# ltc2934_platine.net
KiCad netlist of a schematic drawn in EAGLE
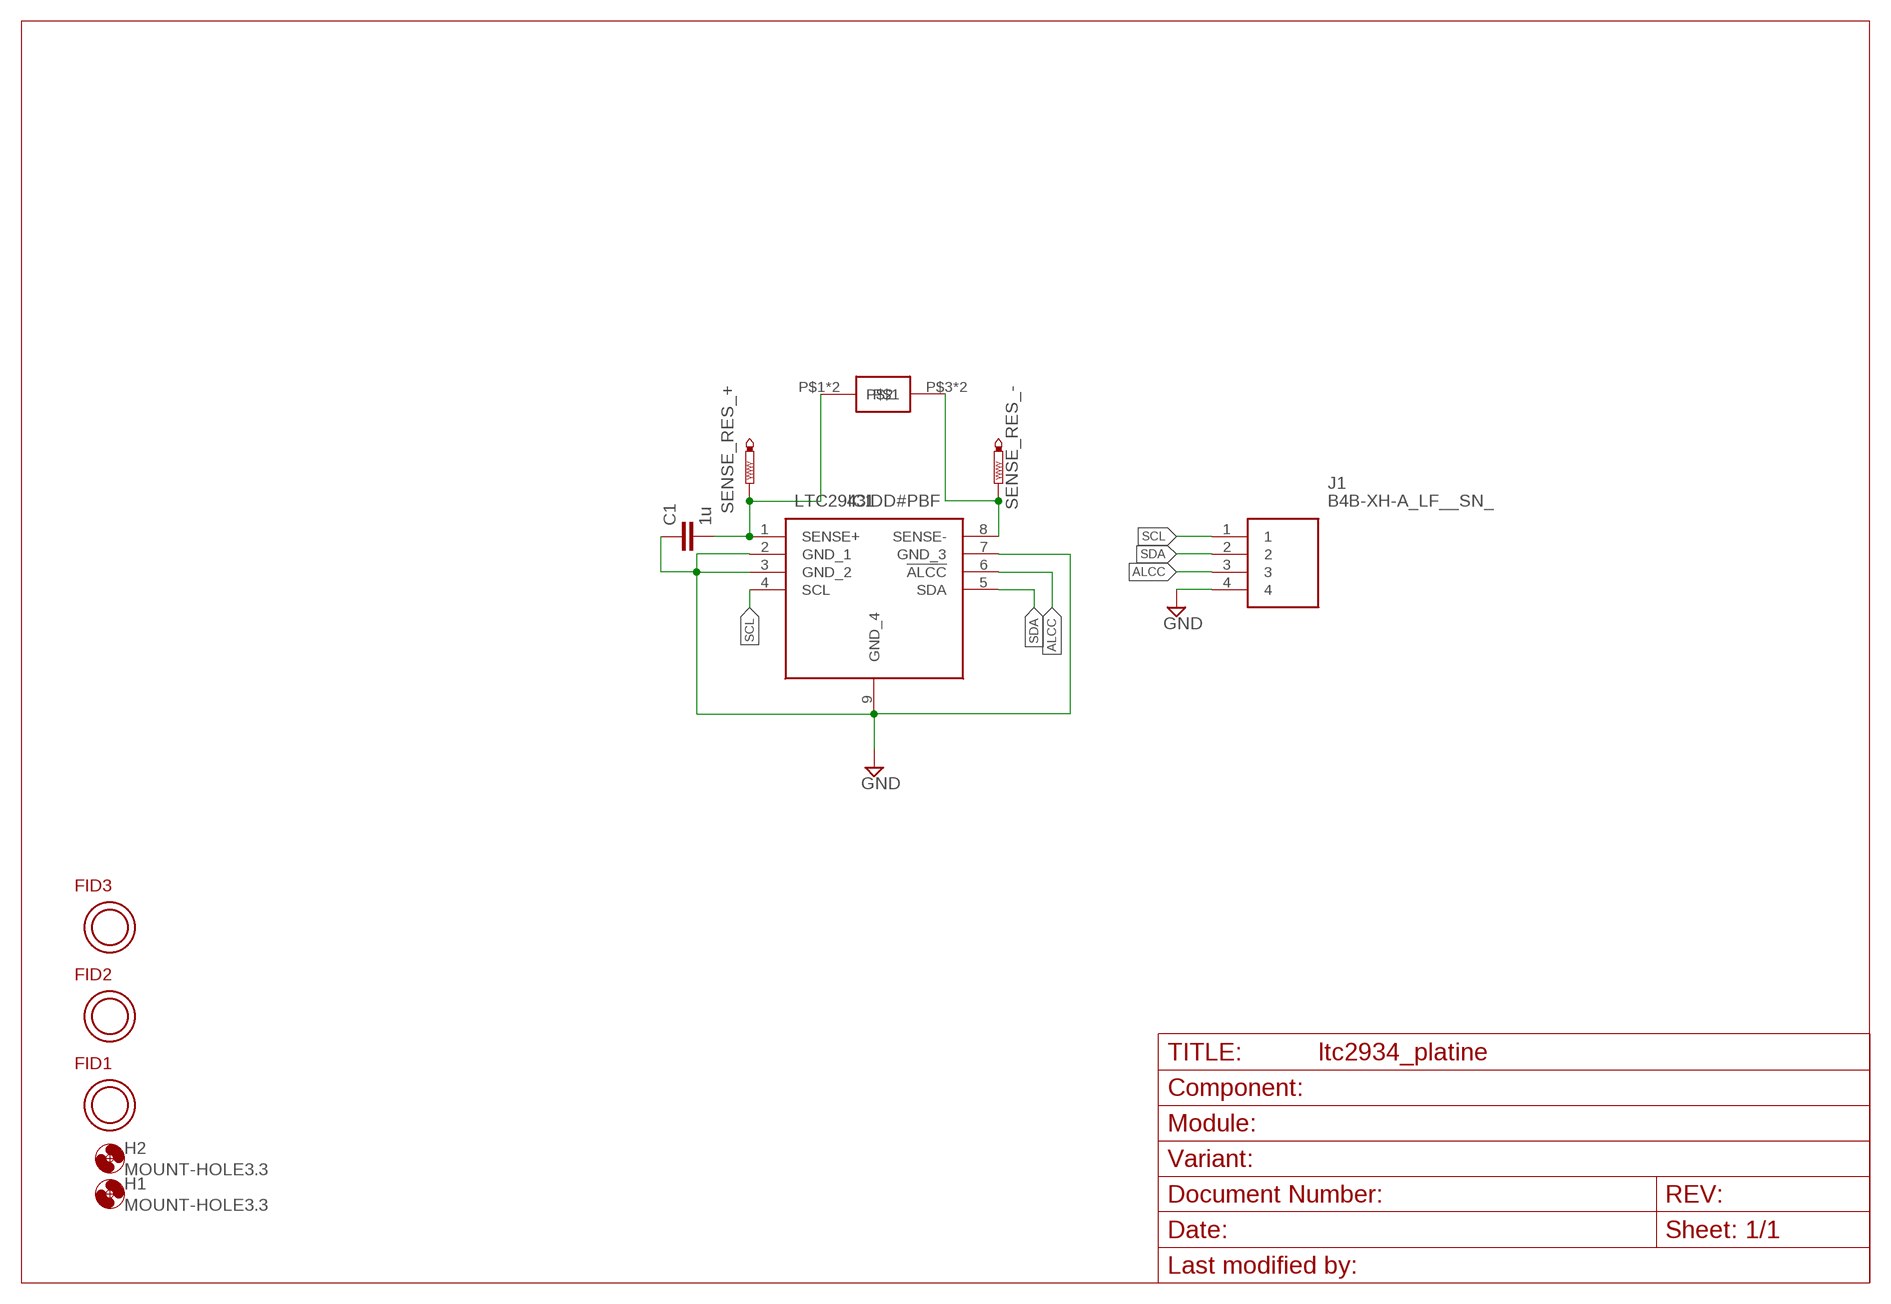
[diagram p0: schematic, sheet 1]

(export (version "E")
  (design (tool "Eeschema 10.0.6"))
  (components
    (comp (ref "C1")
      (value "1u")
      (footprint "eagle-import:C1206")
      (libsource (lib "eagle-import") (part "C-EUC1206"))
    )
    (comp (ref "FID1")
      (value "OPEN-PNP-FIDUCIAL")
      (footprint "eagle-import:OPEN-PNP-FIDUCIAL")
      (libsource (lib "eagle-import") (part "OPEN-PNP-FIDUCIAL"))
    )
    (comp (ref "FID2")
      (value "OPEN-PNP-FIDUCIAL")
      (footprint "eagle-import:OPEN-PNP-FIDUCIAL")
      (libsource (lib "eagle-import") (part "OPEN-PNP-FIDUCIAL"))
    )
    (comp (ref "FID3")
      (value "OPEN-PNP-FIDUCIAL")
      (footprint "eagle-import:OPEN-PNP-FIDUCIAL")
      (libsource (lib "eagle-import") (part "OPEN-PNP-FIDUCIAL"))
    )
    (comp (ref "H1")
      (value "MOUNT-HOLE3.3")
      (footprint "eagle-import:3,3")
      (libsource (lib "eagle-import") (part "MOUNT-HOLE3.3"))
    )
    (comp (ref "H2")
      (value "MOUNT-HOLE3.3")
      (footprint "eagle-import:3,3")
      (libsource (lib "eagle-import") (part "MOUNT-HOLE3.3"))
    )
    (comp (ref "IC1")
      (value "LTC2943IDD#PBF")
      (footprint "eagle-import:SON50P300X300X80-9N")
      (fields (field (name "MOUSER_PART_NUMBER") "584-LTC2943IDD#PBF"))
      (libsource (lib "eagle-import") (part "LTC2943IDD#PBF"))
    )
    (comp (ref "J1")
      (value "B4B-XH-A_LF__SN_")
      (footprint "eagle-import:B4BXHALFSN")
      (fields (field (name "ARROW_PART_NUMBER") "B4B-XH-A(LF)(SN)"))
      (libsource (lib "eagle-import") (part "B4B-XH-A_LF__SN_"))
    )
    (comp (ref "SENSE_RES_+")
      (value "PTR1PAD1-13Y")
      (footprint "eagle-import:P1-13Y")
      (libsource (lib "eagle-import") (part "PTR1PAD1-13Y"))
    )
    (comp (ref "SENSE_RES_-")
      (value "PTR1PAD1-13Y")
      (footprint "eagle-import:P1-13Y")
      (libsource (lib "eagle-import") (part "PTR1PAD1-13Y"))
    )
    (comp (ref "U$1")
      (value "SHUNT_50A_75MV")
      (footprint "eagle-import:SHUNT_50A_75MV")
      (libsource (lib "eagle-import") (part "SHUNT_50A_75MV"))
    )
  )
  (nets
    (net (code "1") (name "ALCC") (class "Default")
      (node (ref "IC1") (pin "6") (pinfunction "~{ALCC}_6") (pintype "bidirectional"))
      (node (ref "J1") (pin "3") (pinfunction "3_3") (pintype "bidirectional"))
    )
    (net (code "2") (name "GND") (class "Default")
      (node (ref "C1") (pin "1") (pinfunction "1_1") (pintype "passive"))
      (node (ref "IC1") (pin "2") (pinfunction "GND_1_2") (pintype "bidirectional"))
      (node (ref "IC1") (pin "3") (pinfunction "GND_2_3") (pintype "bidirectional"))
      (node (ref "IC1") (pin "7") (pinfunction "GND_3_7") (pintype "bidirectional"))
      (node (ref "IC1") (pin "9") (pinfunction "GND_4_9") (pintype "bidirectional"))
      (node (ref "J1") (pin "4") (pinfunction "4_4") (pintype "bidirectional"))
    )
    (net (code "3") (name "Net-(IC1-SENSE+)") (class "Default")
      (node (ref "C1") (pin "2") (pinfunction "2_2") (pintype "passive"))
      (node (ref "IC1") (pin "1") (pinfunction "SENSE+_1") (pintype "bidirectional"))
      (node (ref "SENSE_RES_+") (pin "TP") (pinfunction "TP_TP") (pintype "input"))
      (node (ref "U$1") (pin "P$1") (pinfunction "P$1_P$1") (pintype "bidirectional"))
      (node (ref "U$1") (pin "P$6") (pinfunction "P$1_P$6") (pintype "bidirectional"))
    )
    (net (code "4") (name "Net-(IC1-SENSE-)") (class "Default")
      (node (ref "IC1") (pin "8") (pinfunction "SENSE-_8") (pintype "bidirectional"))
      (node (ref "SENSE_RES_-") (pin "TP") (pinfunction "TP_TP") (pintype "input"))
      (node (ref "U$1") (pin "P$3") (pinfunction "P$2_P$3") (pintype "bidirectional"))
      (node (ref "U$1") (pin "P$5") (pinfunction "P$2_P$5") (pintype "bidirectional"))
    )
    (net (code "5") (name "SCL") (class "Default")
      (node (ref "IC1") (pin "4") (pinfunction "SCL_4") (pintype "bidirectional"))
      (node (ref "J1") (pin "1") (pinfunction "1_1") (pintype "bidirectional"))
    )
    (net (code "6") (name "SDA") (class "Default")
      (node (ref "IC1") (pin "5") (pinfunction "SDA_5") (pintype "bidirectional"))
      (node (ref "J1") (pin "2") (pinfunction "2_2") (pintype "bidirectional"))
    )
  )
)
